# CH1-Input.net
KiCad netlist of a schematic drawn in Altium Designer
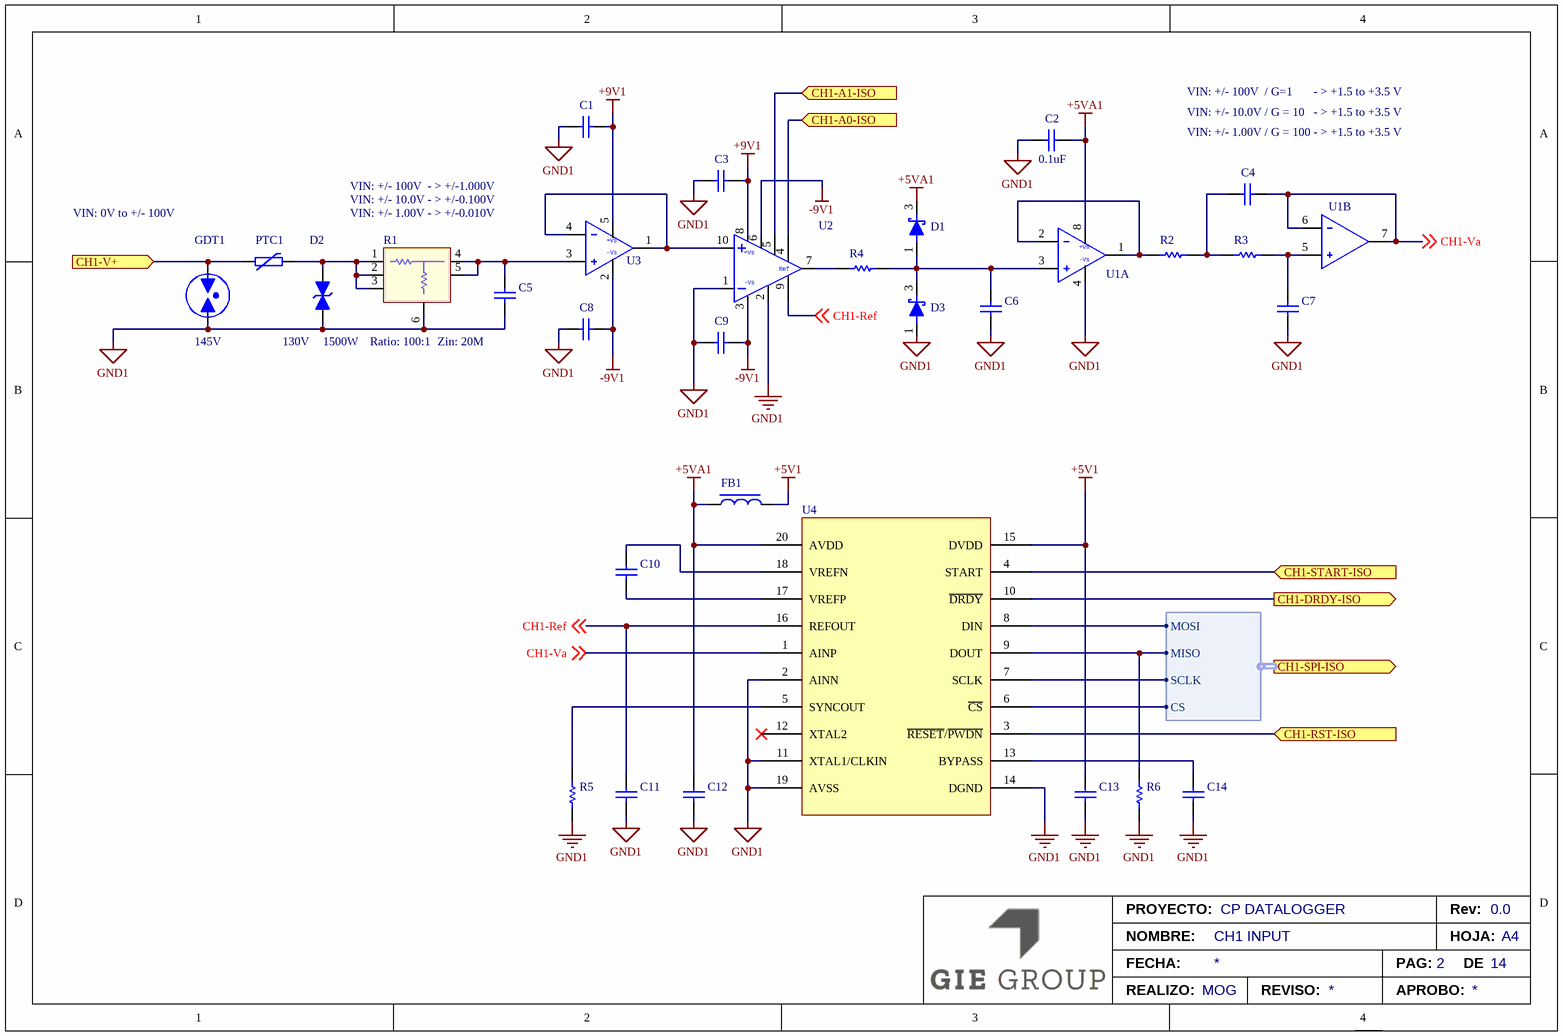
[diagram p0: CH1-Input.SchDoc]

(export (version "E")
  (design (tool "Eeschema 10.0.6"))
  (components
    (comp (ref "C1")
      (value "C0603C104K5RACAUTO")
      (footprint "CAP-0603")
      (description "CAP CER 0.1uF 50V X7R 0603")
      (fields (field (name "MANUFACTURER") "Kemet") (field (name "TOLERANCE") "10%"))
      (libsource (lib "Kemet") (part "C0603C104K5RACAUTO"))
    )
    (comp (ref "C2")
      (value "0.1uF")
      (footprint "CAP-0603")
      (description "CAP CER 0.1uF 50V X7R 0603")
      (fields (field (name "PARTNUMBER") "C0603C104K5RACAUTO") (field (name "MANUFACTURER") "Kemet"))
      (libsource (lib "Kemet") (part "C0603C104K5RACAUTO"))
    )
    (comp (ref "C3")
      (value "C0603C104K5RACAUTO")
      (footprint "CAP-0603")
      (description "CAP CER 0.1uF 50V X7R 0603")
      (fields (field (name "MANUFACTURER") "Kemet") (field (name "TOLERANCE") "10%"))
      (libsource (lib "Kemet") (part "C0603C104K5RACAUTO"))
    )
    (comp (ref "C4")
      (value "C0603C162J5GAC7867")
      (footprint "CAP-0603")
      (description "CAP CER 1600´pF 50V C0G 0603")
      (fields (field (name "MANUFACTURER") "Kemet") (field (name "TOLERANCE") "5%"))
      (libsource (lib "Kemet") (part "C0603C162J5GAC7867"))
    )
    (comp (ref "C5")
      (value "C0603C161J1GAC7867")
      (footprint "CAP-0603")
      (description "CAP CER 750´pF 50V C0G 0603")
      (fields (field (name "MANUFACTURER") "Kemet") (field (name "TOLERANCE") "5%"))
      (libsource (lib "Kemet") (part "C0603C751J5GAC7867"))
    )
    (comp (ref "C6")
      (value "C0603C162J5GAC7867")
      (footprint "CAP-0603")
      (description "CAP CER 1600´pF 50V C0G 0603")
      (fields (field (name "MANUFACTURER") "Kemet") (field (name "TOLERANCE") "5%"))
      (libsource (lib "Kemet") (part "C0603C162J5GAC7867"))
    )
    (comp (ref "C7")
      (value "C0603C161J1GAC7867")
      (footprint "CAP-0603")
      (description "CAP CER 160 pF 100V C0G 0603")
      (fields (field (name "MANUFACTURER") "Kemet") (field (name "TOLERANCE") "5%"))
      (libsource (lib "Kemet") (part "C0603C161J1GAC7867"))
    )
    (comp (ref "C8")
      (value "C0603C104K5RACAUTO")
      (footprint "CAP-0603")
      (description "CAP CER 0.1uF 50V X7R 0603")
      (fields (field (name "MANUFACTURER") "Kemet") (field (name "TOLERANCE") "10%"))
      (libsource (lib "Kemet") (part "C0603C104K5RACAUTO"))
    )
    (comp (ref "C9")
      (value "C0603C104K5RACAUTO")
      (footprint "CAP-0603")
      (description "CAP CER 0.1uF 50V X7R 0603")
      (fields (field (name "MANUFACTURER") "Kemet") (field (name "TOLERANCE") "10%"))
      (libsource (lib "Kemet") (part "C0603C104K5RACAUTO"))
    )
    (comp (ref "C10")
      (value "C0603C105M3RAC7867")
      (footprint "CAP-0603")
      (description "CAP CER 1uF 25V X7R 0603")
      (fields (field (name "MANUFACTURER") "Kemet") (field (name "TOLERANCE") "20%"))
      (libsource (lib "Kemet") (part "C0603C105M3RAC7867"))
    )
    (comp (ref "C11")
      (value "C0603C105M3RAC7867")
      (footprint "CAP-0603")
      (description "CAP CER 1uF 25V X7R 0603")
      (fields (field (name "MANUFACTURER") "Kemet") (field (name "TOLERANCE") "20%"))
      (libsource (lib "Kemet") (part "C0603C105M3RAC7867"))
    )
    (comp (ref "C12")
      (value "C0603C105M3RAC7867")
      (footprint "CAP-0603")
      (description "CAP CER 1uF 25V X7R 0603")
      (fields (field (name "MANUFACTURER") "Kemet") (field (name "TOLERANCE") "20%"))
      (libsource (lib "Kemet") (part "C0603C105M3RAC7867"))
    )
    (comp (ref "C13")
      (value "C0603C105M3RAC7867")
      (footprint "CAP-0603")
      (description "CAP CER 1uF 25V X7R 0603")
      (fields (field (name "MANUFACTURER") "Kemet") (field (name "TOLERANCE") "20%"))
      (libsource (lib "Kemet") (part "C0603C105M3RAC7867"))
    )
    (comp (ref "C14")
      (value "C0603C105M3RAC7867")
      (footprint "CAP-0603")
      (description "CAP CER 1uF 25V X7R 0603")
      (fields (field (name "MANUFACTURER") "Kemet") (field (name "TOLERANCE") "20%"))
      (libsource (lib "Kemet") (part "C0603C105M3RAC7867"))
    )
    (comp (ref "D1")
      (value "NSVBAT54WT1G")
      (footprint "SOT-323-3")
      (description "Schottky Diode 30V 200mA SOT323")
      (fields (field (name "MANUFACTURER") "OnSemiconductor"))
      (libsource (lib "OnSemiconductors") (part "NSVBAT54WT1G"))
    )
    (comp (ref "D2")
      (value "~")
      (footprint "SMC - BIIDIR")
      (description "TVS Diode 1.5kW 130V 5% Bi-Directional")
      (fields
        (field (name "MANUFACTURER") "Littelfuse")
        (field (name "VOLTAGE") "130V")
        (field (name "POWER") "1500W")
      )
      (libsource (lib "Littlelfuse") (part "1.5SMC130CA"))
    )
    (comp (ref "D3")
      (value "~")
      (footprint "SOT-323-3")
      (description "Schottky Diode 30V 200mA SOT323")
      (fields (field (name "MANUFACTURER") "OnSemiconductor"))
      (libsource (lib "OnSemiconductors") (part "NSVBAT54WT1G"))
    )
    (comp (ref "FB1")
      (value "Z0603C121GPWZT")
      (footprint "IND-0603")
      (description "Ferrite Bead 120Ohms 900mA 25% DCR=130m")
      (fields (field (name "MANUFACTURER") "Kemet"))
      (libsource (lib "Kemet") (part "Z0603C121GPWZT"))
    )
    (comp (ref "GDT1")
      (value "~")
      (footprint "LITTLELFUSE-CG5XXXLTR")
      (description "Gas Discharge Tube 145V")
      (fields (field (name "MANUFACTURER") "Littelfuse") (field (name "VOLTAGE") "145V"))
      (libsource (lib "Littlelfuse") (part "CG5145LTR"))
    )
    (comp (ref "PTC1")
      (value "~")
      (footprint "LITTLELFUSE-72R020X")
      (description "PTC Polyfuse Radial 72V 0.2A")
      (fields (field (name "MANUFACTURER") "Littlelfuse"))
      (libsource (lib "Littlelfuse") (part "72R020XPR"))
    )
    (comp (ref "R1")
      (value "~")
      (footprint "CADDOCK - HVD5-B20M-050-05")
      (description "20M ohm 0.05% 5ppm Voltage Divider")
      (fields
        (field (name "MANUFACTURER") "Caddock")
        (field (name "RATIO") "100:1")
        (field (name "ZIN") "20M")
      )
      (libsource (lib "Caddock") (part "HVD5-B20M-050-05"))
    )
    (comp (ref "R2")
      (value "RC0603FR-07113KL")
      (footprint "RES-0603")
      (description "RES SMD 113K OHM 1% 1/10W 0603")
      (fields (field (name "TOLERANCE") "1%") (field (name "MANUFACTURER") "Yageo"))
      (libsource (lib "Yageo") (part "RC0603FR-07113KL"))
    )
    (comp (ref "R3")
      (value "RC0603FR-07887KL")
      (footprint "RES-0603")
      (description "RES SMD 887K OHM 1% 1/10W 0603")
      (fields (field (name "TOLERANCE") "1%") (field (name "MANUFACTURER") "Yageo"))
      (libsource (lib "Yageo") (part "RC0603FR-07887KL"))
    )
    (comp (ref "R4")
      (value "RC0603FR-07100KL")
      (footprint "RES-0603")
      (description "RES SMD 100K OHM 1% 1/10W 0603")
      (fields (field (name "TOLERANCE") "1%") (field (name "MANUFACTURER") "Yageo"))
      (libsource (lib "Yageo") (part "RC0603FR-07100KL"))
    )
    (comp (ref "R5")
      (value "RC0603FR-071ML")
      (footprint "RES-0603")
      (description "RES SMD 1M OHM 1% 1/10W 0603")
      (fields (field (name "TOLERANCE") "1%") (field (name "MANUFACTURER") "Yageo"))
      (libsource (lib "Yageo") (part "RC0603FR-071ML"))
    )
    (comp (ref "R6")
      (value "RC0603FR-071ML")
      (footprint "RES-0603")
      (description "RES SMD 1M OHM 1% 1/10W 0603")
      (fields (field (name "TOLERANCE") "1%") (field (name "MANUFACTURER") "Yageo"))
      (libsource (lib "Yageo") (part "RC0603FR-071ML"))
    )
    (comp (ref "U1")
      (value "~")
      (footprint "MSOP8")
      (description "Dual  Precision Amplifier Micro Power Auto Zero")
      (fields (field (name "MANUFACTURER") "Analog Devices"))
      (libsource (lib "AnalogDevices") (part "ADA4051-2ARMZ"))
    )
    (comp (ref "U2")
      (value "AD8253ARMZ")
      (footprint "MSOP10")
      (description "Instrumentation Amplifiers High Speed Programmable High Gain In-Amp")
      (fields (field (name "MANUFACTURER") "Analog Devices Inc"))
      (libsource (lib "AnalogDevices") (part "AD8253ARMZ"))
    )
    (comp (ref "U3")
      (value "~")
      (footprint "SOT23-5")
      (description "16V Auto-Zero CMOS Amplifier")
      (fields (field (name "MANUFACTURER") "Analog Devices"))
      (libsource (lib "AnalogDevices") (part "AD8638ARJZ"))
    )
    (comp (ref "U4")
      (value "~")
      (footprint "TSSOP20")
      (description "Analog to Digital Converter 14.4kSPS 24-Bit")
      (fields (field (name "MANUFACTURER") "Texas Instruments"))
      (libsource (lib "TexasInstruments") (part "ADS1259BIPW"))
    )
  )
  (nets
    (net (code "2") (name "+5V1") (class "Default")
      (node (ref "C13") (pin "2") (pinfunction "2_2") (pintype "passive"))
      (node (ref "FB1") (pin "2") (pinfunction "2_2") (pintype "passive"))
      (node (ref "U4") (pin "15") (pinfunction "DVDD_15") (pintype "power_in"))
    )
    (net (code "3") (name "+5VA1") (class "Default")
      (node (ref "C12") (pin "2") (pinfunction "2_2") (pintype "passive"))
      (node (ref "C2") (pin "2") (pinfunction "2_2") (pintype "passive"))
      (node (ref "D1") (pin "3") (pinfunction "K_3") (pintype "passive"))
      (node (ref "FB1") (pin "1") (pinfunction "1_1") (pintype "passive"))
      (node (ref "U1") (pin "8") (pinfunction "+VS_8") (pintype "power_in"))
      (node (ref "U4") (pin "20") (pinfunction "AVDD_20") (pintype "power_in"))
    )
    (net (code "4") (name "+9V1") (class "Default")
      (node (ref "C1") (pin "2") (pinfunction "2_2") (pintype "passive"))
      (node (ref "C3") (pin "2") (pinfunction "2_2") (pintype "passive"))
      (node (ref "U2") (pin "8") (pinfunction "+Vs_8") (pintype "passive"))
      (node (ref "U3") (pin "5") (pinfunction "+VS_5") (pintype "power_in"))
    )
    (net (code "5") (name "-9V1") (class "Default")
      (node (ref "C8") (pin "2") (pinfunction "2_2") (pintype "passive"))
      (node (ref "C9") (pin "2") (pinfunction "2_2") (pintype "passive"))
      (node (ref "U2") (pin "3") (pinfunction "-Vs_3") (pintype "passive"))
      (node (ref "U2") (pin "6") (pinfunction "WR_6") (pintype "passive"))
      (node (ref "U3") (pin "2") (pinfunction "-Vs_2") (pintype "power_in"))
    )
    (net (code "6") (name "/CH1-A0-ISO") (class "Default")
      (node (ref "U2") (pin "4") (pinfunction "A0_4") (pintype "passive"))
    )
    (net (code "7") (name "/CH1-A1-ISO") (class "Default")
      (node (ref "U2") (pin "5") (pinfunction "A1_5") (pintype "passive"))
    )
    (net (code "8") (name "/CH1-DRDY-ISO") (class "Default")
      (node (ref "U4") (pin "10") (pinfunction "~{DRDY}_10") (pintype "power_in"))
    )
    (net (code "9") (name "/CH1-RST-ISO") (class "Default")
      (node (ref "U4") (pin "3") (pinfunction "~{RESET}/~{PWDN}_3") (pintype "power_in"))
    )
    (net (code "10") (name "/CH1-START-ISO") (class "Default")
      (node (ref "U4") (pin "4") (pinfunction "START_4") (pintype "power_in"))
    )
    (net (code "11") (name "/CH1-V+") (class "Default")
      (node (ref "GDT1") (pin "1") (pinfunction "A_1") (pintype "passive"))
      (node (ref "PTC1") (pin "1") (pinfunction "1_1") (pintype "passive"))
    )
    (net (code "12") (name "/CS") (class "Default")
      (node (ref "U4") (pin "6") (pinfunction "~{CS}_6") (pintype "power_in"))
    )
    (net (code "13") (name "/MISO") (class "Default")
      (node (ref "R6") (pin "2") (pinfunction "2_2") (pintype "passive"))
      (node (ref "U4") (pin "9") (pinfunction "DOUT_9") (pintype "power_in"))
    )
    (net (code "14") (name "/MOSI") (class "Default")
      (node (ref "U4") (pin "8") (pinfunction "DIN_8") (pintype "power_in"))
    )
    (net (code "15") (name "/SCLK") (class "Default")
      (node (ref "U4") (pin "7") (pinfunction "SCLK_7") (pintype "power_in"))
    )
    (net (code "17") (name "CH1-Ref") (class "Default")
      (node (ref "C11") (pin "2") (pinfunction "2_2") (pintype "passive"))
      (node (ref "U2") (pin "9") (pinfunction "REF_9") (pintype "passive"))
      (node (ref "U4") (pin "16") (pinfunction "REFOUT_16") (pintype "power_in"))
    )
    (net (code "18") (name "CH1-Va") (class "Default")
      (node (ref "C4") (pin "1") (pinfunction "1_1") (pintype "passive"))
      (node (ref "U1") (pin "6") (pinfunction "-INB_6") (pintype "passive"))
      (node (ref "U1") (pin "7") (pinfunction "OUTB_7") (pintype "passive"))
      (node (ref "U4") (pin "1") (pinfunction "AINP_1") (pintype "passive"))
    )
    (net (code "19") (name "GND1") (class "Default")
      (node (ref "C1") (pin "1") (pinfunction "1_1") (pintype "passive"))
      (node (ref "C11") (pin "1") (pinfunction "1_1") (pintype "passive"))
      (node (ref "C12") (pin "1") (pinfunction "1_1") (pintype "passive"))
      (node (ref "C13") (pin "1") (pinfunction "1_1") (pintype "passive"))
      (node (ref "C14") (pin "1") (pinfunction "1_1") (pintype "passive"))
      (node (ref "C2") (pin "1") (pinfunction "1_1") (pintype "passive"))
      (node (ref "C3") (pin "1") (pinfunction "1_1") (pintype "passive"))
      (node (ref "C5") (pin "1") (pinfunction "1_1") (pintype "passive"))
      (node (ref "C6") (pin "1") (pinfunction "1_1") (pintype "passive"))
      (node (ref "C7") (pin "1") (pinfunction "1_1") (pintype "passive"))
      (node (ref "C8") (pin "1") (pinfunction "1_1") (pintype "passive"))
      (node (ref "C9") (pin "1") (pinfunction "1_1") (pintype "passive"))
      (node (ref "D2") (pin "2") (pinfunction "K_2") (pintype "passive"))
      (node (ref "D3") (pin "1") (pinfunction "A_1") (pintype "passive"))
      (node (ref "GDT1") (pin "2") (pinfunction "K_2") (pintype "passive"))
      (node (ref "R1") (pin "6") (pinfunction "6_6") (pintype "passive"))
      (node (ref "R5") (pin "1") (pinfunction "1_1") (pintype "passive"))
      (node (ref "R6") (pin "1") (pinfunction "1_1") (pintype "passive"))
      (node (ref "U1") (pin "4") (pinfunction "-Vs_4") (pintype "power_in"))
      (node (ref "U2") (pin "1") (pinfunction "-_IN_1") (pintype "passive"))
      (node (ref "U2") (pin "2") (pinfunction "DGND_2") (pintype "passive"))
      (node (ref "U4") (pin "11") (pinfunction "XTAL1/CLKIN_11") (pintype "power_in"))
      (node (ref "U4") (pin "14") (pinfunction "DGND_14") (pintype "power_in"))
      (node (ref "U4") (pin "19") (pinfunction "AVSS_19") (pintype "power_in"))
      (node (ref "U4") (pin "2") (pinfunction "AINN_2") (pintype "passive"))
    )
    (net (code "20") (name "Net-(C4-Pad2)") (class "Default")
      (node (ref "C4") (pin "2") (pinfunction "2_2") (pintype "passive"))
      (node (ref "R2") (pin "2") (pinfunction "2_2") (pintype "passive"))
      (node (ref "R3") (pin "1") (pinfunction "1_1") (pintype "passive"))
    )
    (net (code "21") (name "Net-(D1-A)") (class "Default")
      (node (ref "C6") (pin "2") (pinfunction "2_2") (pintype "passive"))
      (node (ref "D1") (pin "1") (pinfunction "A_1") (pintype "passive"))
      (node (ref "D3") (pin "3") (pinfunction "K_3") (pintype "passive"))
      (node (ref "R4") (pin "2") (pinfunction "2_2") (pintype "passive"))
      (node (ref "U1") (pin "3") (pinfunction "+INA_3") (pintype "passive"))
    )
    (net (code "22") (name "Net-(D2-A)") (class "Default")
      (node (ref "D2") (pin "1") (pinfunction "A_1") (pintype "passive"))
      (node (ref "PTC1") (pin "2") (pinfunction "2_2") (pintype "passive"))
      (node (ref "R1") (pin "1") (pinfunction "1_1") (pintype "passive"))
      (node (ref "R1") (pin "2") (pinfunction "2_2") (pintype "passive"))
      (node (ref "R1") (pin "3") (pinfunction "3_3") (pintype "passive"))
    )
    (net (code "23") (name "Net-(U1A--INA)") (class "Default")
      (node (ref "R2") (pin "1") (pinfunction "1_1") (pintype "passive"))
      (node (ref "U1") (pin "1") (pinfunction "OUTA_1") (pintype "passive"))
      (node (ref "U1") (pin "2") (pinfunction "-INA_2") (pintype "passive"))
    )
    (net (code "24") (name "Net-(U1B-+INB)") (class "Default")
      (node (ref "C7") (pin "2") (pinfunction "2_2") (pintype "passive"))
      (node (ref "R3") (pin "2") (pinfunction "2_2") (pintype "passive"))
      (node (ref "U1") (pin "5") (pinfunction "+INB_5") (pintype "passive"))
    )
    (net (code "25") (name "Net-(U2-+_IN)") (class "Default")
      (node (ref "U2") (pin "10") (pinfunction "+_IN_10") (pintype "passive"))
      (node (ref "U3") (pin "1") (pinfunction "OUT_1") (pintype "passive"))
      (node (ref "U3") (pin "4") (pinfunction "-IN_4") (pintype "passive"))
    )
    (net (code "26") (name "Net-(U2-OUT)") (class "Default")
      (node (ref "R4") (pin "1") (pinfunction "1_1") (pintype "passive"))
      (node (ref "U2") (pin "7") (pinfunction "OUT_7") (pintype "passive"))
    )
    (net (code "27") (name "Net-(U3-+IN)") (class "Default")
      (node (ref "C5") (pin "2") (pinfunction "2_2") (pintype "passive"))
      (node (ref "R1") (pin "4") (pinfunction "4_4") (pintype "passive"))
      (node (ref "R1") (pin "5") (pinfunction "5_5") (pintype "passive"))
      (node (ref "U3") (pin "3") (pinfunction "+IN_3") (pintype "passive"))
    )
    (net (code "28") (name "Net-(U4-BYPASS)") (class "Default")
      (node (ref "C14") (pin "2") (pinfunction "2_2") (pintype "passive"))
      (node (ref "U4") (pin "13") (pinfunction "BYPASS_13") (pintype "power_in"))
    )
    (net (code "29") (name "Net-(U4-SYNCOUT)") (class "Default")
      (node (ref "R5") (pin "2") (pinfunction "2_2") (pintype "passive"))
      (node (ref "U4") (pin "5") (pinfunction "SYNCOUT_5") (pintype "passive"))
    )
    (net (code "30") (name "Net-(U4-VREFN)") (class "Default")
      (node (ref "C10") (pin "2") (pinfunction "2_2") (pintype "passive"))
      (node (ref "U4") (pin "18") (pinfunction "VREFN_18") (pintype "power_in"))
    )
    (net (code "31") (name "Net-(U4-VREFP)") (class "Default")
      (node (ref "C10") (pin "1") (pinfunction "1_1") (pintype "passive"))
      (node (ref "U4") (pin "17") (pinfunction "VREFP_17") (pintype "power_in"))
    )
    (net (code "32") (name "unconnected-(U4-XTAL2-Pad12)") (class "Default")
      (node (ref "U4") (pin "12") (pinfunction "XTAL2_12") (pintype "power_in+no_connect"))
    )
  )
)
